# scc.net
KiCad netlist of a schematic drawn in EAGLE
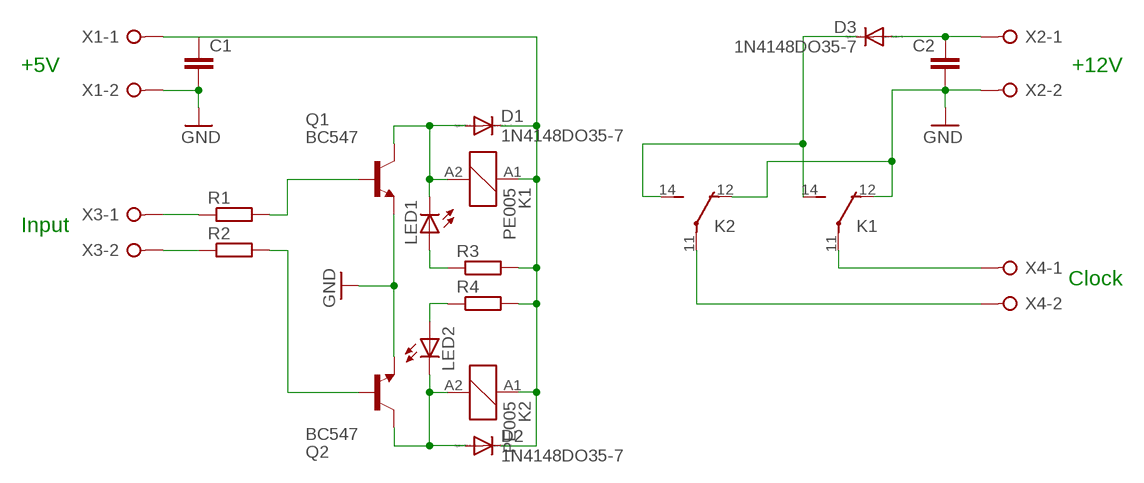
[diagram p0: schematic, sheet 1]

(export (version "E")
  (design (tool "Eeschema 10.0.6"))
  (components
    (comp (ref "C1")
      (value "C-EU050-024X044")
      (footprint "eagle-import:C050-024X044")
      (libsource (lib "eagle-import") (part "C-EU050-024X044"))
    )
    (comp (ref "C2")
      (value "C-EU050-024X044")
      (footprint "eagle-import:C050-024X044")
      (libsource (lib "eagle-import") (part "C-EU050-024X044"))
    )
    (comp (ref "D1")
      (value "1N4148DO35-7")
      (footprint "eagle-import:DO35-7")
      (libsource (lib "eagle-import") (part "1N4148DO35-7"))
    )
    (comp (ref "D2")
      (value "1N4148DO35-7")
      (footprint "eagle-import:DO35-7")
      (libsource (lib "eagle-import") (part "1N4148DO35-7"))
    )
    (comp (ref "D3")
      (value "1N4148DO35-7")
      (footprint "eagle-import:DO35-7")
      (libsource (lib "eagle-import") (part "1N4148DO35-7"))
    )
    (comp (ref "K1")
      (value "PE005")
      (footprint "eagle-import:PE")
      (libsource (lib "eagle-import") (part "PE005"))
    )
    (comp (ref "K2")
      (value "PE005")
      (footprint "eagle-import:PE")
      (libsource (lib "eagle-import") (part "PE005"))
    )
    (comp (ref "LED1")
      (value "LED3MM")
      (footprint "eagle-import:LED3MM")
      (libsource (lib "eagle-import") (part "LED3MM"))
    )
    (comp (ref "LED2")
      (value "LED3MM")
      (footprint "eagle-import:LED3MM")
      (libsource (lib "eagle-import") (part "LED3MM"))
    )
    (comp (ref "Q1")
      (value "BC547")
      (footprint "eagle-import:TO92")
      (libsource (lib "eagle-import") (part "BC547"))
    )
    (comp (ref "Q2")
      (value "BC547")
      (footprint "eagle-import:TO92")
      (libsource (lib "eagle-import") (part "BC547"))
    )
    (comp (ref "R1")
      (value "R-EU_0204/7")
      (footprint "eagle-import:0204_7")
      (libsource (lib "eagle-import") (part "R-EU_0204/7"))
    )
    (comp (ref "R2")
      (value "R-EU_0204/7")
      (footprint "eagle-import:0204_7")
      (libsource (lib "eagle-import") (part "R-EU_0204/7"))
    )
    (comp (ref "R3")
      (value "R-EU_0204/7")
      (footprint "eagle-import:0204_7")
      (libsource (lib "eagle-import") (part "R-EU_0204/7"))
    )
    (comp (ref "R4")
      (value "R-EU_0204/7")
      (footprint "eagle-import:0204_7")
      (libsource (lib "eagle-import") (part "R-EU_0204/7"))
    )
    (comp (ref "X1")
      (value "W237-02P")
      (footprint "eagle-import:W237-132")
      (libsource (lib "eagle-import") (part "W237-02P"))
    )
    (comp (ref "X2")
      (value "W237-02P")
      (footprint "eagle-import:W237-132")
      (libsource (lib "eagle-import") (part "W237-02P"))
    )
    (comp (ref "X3")
      (value "W237-02P")
      (footprint "eagle-import:W237-132")
      (libsource (lib "eagle-import") (part "W237-02P"))
    )
    (comp (ref "X4")
      (value "W237-02P")
      (footprint "eagle-import:W237-132")
      (libsource (lib "eagle-import") (part "W237-02P"))
    )
  )
  (nets
    (net (code "1") (name "GND") (class "Default")
      (node (ref "C1") (pin "2") (pinfunction "2_2") (pintype "passive"))
      (node (ref "C2") (pin "2") (pinfunction "2_2") (pintype "passive"))
      (node (ref "K1") (pin "12") (pinfunction "O_12") (pintype "passive"))
      (node (ref "K2") (pin "12") (pinfunction "O_12") (pintype "passive"))
      (node (ref "Q1") (pin "1") (pinfunction "E_1") (pintype "passive"))
      (node (ref "Q2") (pin "1") (pinfunction "E_1") (pintype "passive"))
      (node (ref "X1") (pin "2") (pinfunction "KL_2") (pintype "passive"))
      (node (ref "X2") (pin "2") (pinfunction "KL_2") (pintype "passive"))
    )
    (net (code "2") (name "Net-(K1A-1)") (class "Default")
      (node (ref "C1") (pin "1") (pinfunction "1_1") (pintype "passive"))
      (node (ref "D1") (pin "C") (pinfunction "C_C") (pintype "passive"))
      (node (ref "D2") (pin "C") (pinfunction "C_C") (pintype "passive"))
      (node (ref "K1") (pin "A1") (pinfunction "1_A1") (pintype "passive"))
      (node (ref "K2") (pin "A1") (pinfunction "1_A1") (pintype "passive"))
      (node (ref "R3") (pin "2") (pinfunction "2_2") (pintype "passive"))
      (node (ref "R4") (pin "2") (pinfunction "2_2") (pintype "passive"))
      (node (ref "X1") (pin "1") (pinfunction "KL_1") (pintype "passive"))
    )
    (net (code "3") (name "Net-(K1A-2)") (class "Default")
      (node (ref "D1") (pin "A") (pinfunction "A_A") (pintype "passive"))
      (node (ref "K1") (pin "A2") (pinfunction "2_A2") (pintype "passive"))
      (node (ref "LED1") (pin "K") (pinfunction "C_K") (pintype "passive"))
      (node (ref "Q1") (pin "3") (pinfunction "C_3") (pintype "passive"))
    )
    (net (code "4") (name "Net-(K1B-P)") (class "Default")
      (node (ref "K1") (pin "11") (pinfunction "P_11") (pintype "passive"))
      (node (ref "X4") (pin "1") (pinfunction "KL_1") (pintype "passive"))
    )
    (net (code "5") (name "Net-(K1B-S)") (class "Default")
      (node (ref "D3") (pin "C") (pinfunction "C_C") (pintype "passive"))
      (node (ref "K1") (pin "14") (pinfunction "S_14") (pintype "passive"))
      (node (ref "K2") (pin "14") (pinfunction "S_14") (pintype "passive"))
    )
    (net (code "6") (name "Net-(K2A-2)") (class "Default")
      (node (ref "D2") (pin "A") (pinfunction "A_A") (pintype "passive"))
      (node (ref "K2") (pin "A2") (pinfunction "2_A2") (pintype "passive"))
      (node (ref "LED2") (pin "K") (pinfunction "C_K") (pintype "passive"))
      (node (ref "Q2") (pin "3") (pinfunction "C_3") (pintype "passive"))
    )
    (net (code "7") (name "Net-(K2B-P)") (class "Default")
      (node (ref "K2") (pin "11") (pinfunction "P_11") (pintype "passive"))
      (node (ref "X4") (pin "2") (pinfunction "KL_2") (pintype "passive"))
    )
    (net (code "8") (name "Net-(LED1-PadA)") (class "Default")
      (node (ref "LED1") (pin "A") (pinfunction "A_A") (pintype "passive"))
      (node (ref "R3") (pin "1") (pinfunction "1_1") (pintype "passive"))
    )
    (net (code "9") (name "Net-(LED2-PadA)") (class "Default")
      (node (ref "LED2") (pin "A") (pinfunction "A_A") (pintype "passive"))
      (node (ref "R4") (pin "1") (pinfunction "1_1") (pintype "passive"))
    )
    (net (code "10") (name "Net-(Q1-B)") (class "Default")
      (node (ref "Q1") (pin "2") (pinfunction "B_2") (pintype "passive"))
      (node (ref "R1") (pin "2") (pinfunction "2_2") (pintype "passive"))
    )
    (net (code "11") (name "Net-(Q2-B)") (class "Default")
      (node (ref "Q2") (pin "2") (pinfunction "B_2") (pintype "passive"))
      (node (ref "R2") (pin "2") (pinfunction "2_2") (pintype "passive"))
    )
    (net (code "12") (name "Net-(X2A-KL)") (class "Default")
      (node (ref "C2") (pin "1") (pinfunction "1_1") (pintype "passive"))
      (node (ref "D3") (pin "A") (pinfunction "A_A") (pintype "passive"))
      (node (ref "X2") (pin "1") (pinfunction "KL_1") (pintype "passive"))
    )
    (net (code "13") (name "Net-(X3A-KL)") (class "Default")
      (node (ref "R1") (pin "1") (pinfunction "1_1") (pintype "passive"))
      (node (ref "X3") (pin "1") (pinfunction "KL_1") (pintype "passive"))
    )
    (net (code "14") (name "Net-(X3B-KL)") (class "Default")
      (node (ref "R2") (pin "1") (pinfunction "1_1") (pintype "passive"))
      (node (ref "X3") (pin "2") (pinfunction "KL_2") (pintype "passive"))
    )
  )
)
